# 1_Main.net
KiCad netlist of a schematic drawn in EAGLE
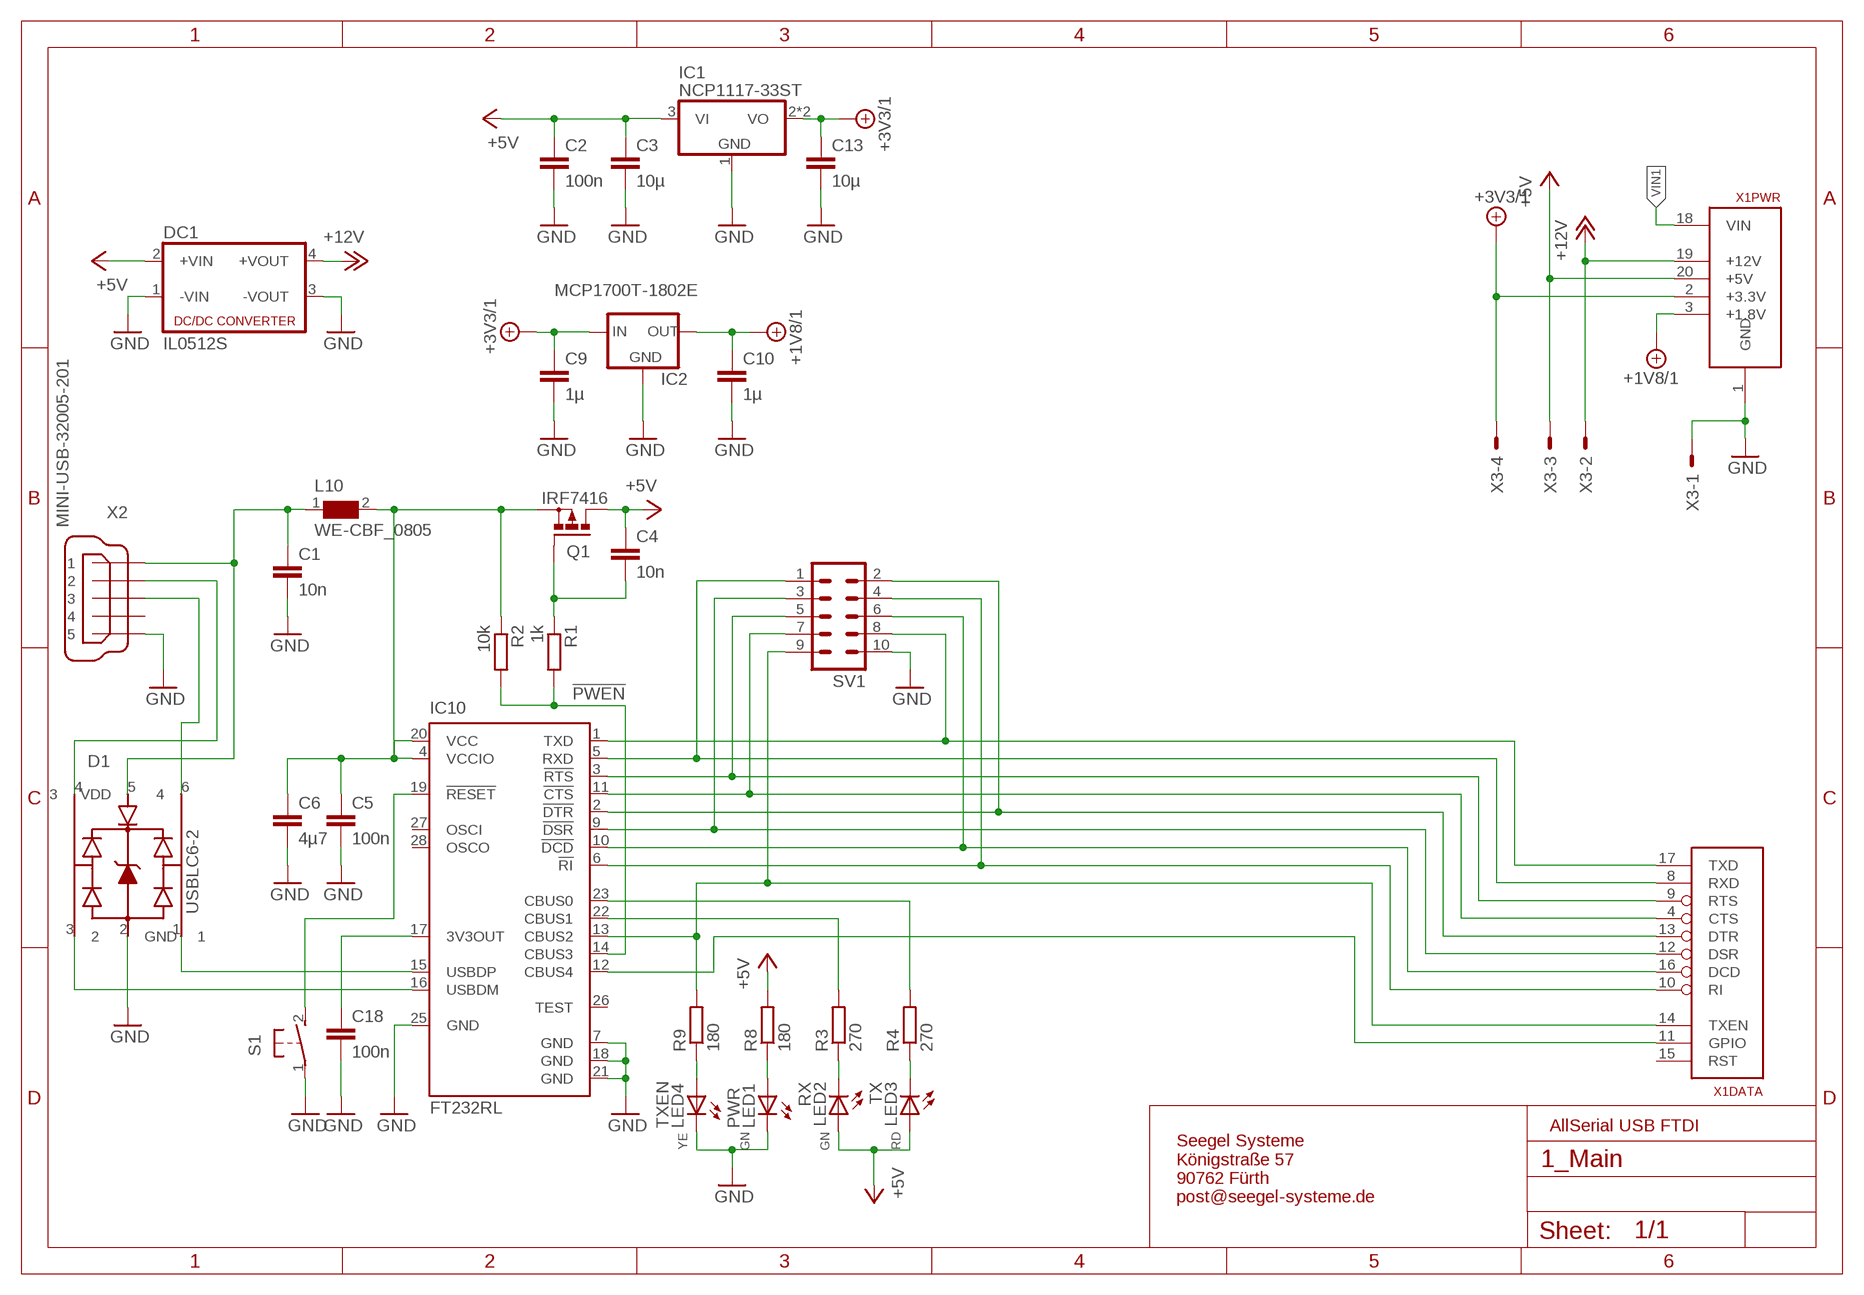
[diagram p0: schematic, sheet 1]

(export (version "E")
  (design (tool "Eeschema 10.0.6"))
  (components
    (comp (ref "C1")
      (value "10n")
      (footprint "eagle-import:C0805")
      (libsource (lib "eagle-import") (part "C-EUC0805"))
    )
    (comp (ref "C2")
      (value "100n")
      (footprint "eagle-import:C0805")
      (libsource (lib "eagle-import") (part "C-EUC0805"))
    )
    (comp (ref "C3")
      (value "10µ")
      (footprint "eagle-import:C0805")
      (libsource (lib "eagle-import") (part "C-EUC0805"))
    )
    (comp (ref "C4")
      (value "10n")
      (footprint "eagle-import:C0805")
      (libsource (lib "eagle-import") (part "C-EUC0805"))
    )
    (comp (ref "C5")
      (value "100n")
      (footprint "eagle-import:C0805")
      (libsource (lib "eagle-import") (part "C-EUC0805"))
    )
    (comp (ref "C6")
      (value "4µ7")
      (footprint "eagle-import:C0805")
      (libsource (lib "eagle-import") (part "C-EUC0805"))
    )
    (comp (ref "C9")
      (value "1µ")
      (footprint "eagle-import:C0805")
      (libsource (lib "eagle-import") (part "C-EUC0805"))
    )
    (comp (ref "C10")
      (value "1µ")
      (footprint "eagle-import:C0805")
      (libsource (lib "eagle-import") (part "C-EUC0805"))
    )
    (comp (ref "C13")
      (value "10µ")
      (footprint "eagle-import:C0805")
      (libsource (lib "eagle-import") (part "C-EUC0805"))
    )
    (comp (ref "C18")
      (value "100n")
      (footprint "eagle-import:C0805")
      (libsource (lib "eagle-import") (part "C-EUC0805"))
    )
    (comp (ref "D1")
      (value "USBLC6-2")
      (footprint "eagle-import:WE-TVS_SOT23-6L")
      (libsource (lib "eagle-import") (part "WE-TVS_82400102"))
    )
    (comp (ref "DC1")
      (value "IL0512S")
      (footprint "eagle-import:NME")
      (fields (field (name "MF") "C & D TECHNOLOGIES, INC") (field (name "MPN") "NME1205D"))
      (libsource (lib "eagle-import") (part "NME"))
    )
    (comp (ref "IC1")
      (value "NCP1117-33ST")
      (footprint "eagle-import:SOT223")
      (libsource (lib "eagle-import") (part "NCP1117ST-33"))
    )
    (comp (ref "IC2")
      (value "MCP1700T-1802E")
      (footprint "eagle-import:SOT23")
      (libsource (lib "eagle-import") (part "MCP170X"))
    )
    (comp (ref "IC10")
      (value "FT232RL")
      (footprint "eagle-import:SSOP28")
      (libsource (lib "eagle-import") (part "FT232RL"))
    )
    (comp (ref "L10")
      (value "WE-CBF_0805")
      (footprint "eagle-import:0805")
      (libsource (lib "eagle-import") (part "WE-CBF_0805"))
    )
    (comp (ref "LED1")
      (value "PWR")
      (footprint "eagle-import:CHIPLED_0603")
      (fields (field (name "COLOR") "GN"))
      (libsource (lib "eagle-import") (part "LEDCHIPLED_0603"))
    )
    (comp (ref "LED2")
      (value "RX")
      (footprint "eagle-import:CHIPLED_0603")
      (fields (field (name "COLOR") "GN"))
      (libsource (lib "eagle-import") (part "LEDCHIPLED_0603"))
    )
    (comp (ref "LED3")
      (value "TX")
      (footprint "eagle-import:CHIPLED_0603")
      (fields (field (name "COLOR") "RD"))
      (libsource (lib "eagle-import") (part "LEDCHIPLED_0603"))
    )
    (comp (ref "LED4")
      (value "TXEN")
      (footprint "eagle-import:CHIPLED_0603")
      (fields (field (name "COLOR") "YE"))
      (libsource (lib "eagle-import") (part "LEDCHIPLED_0603"))
    )
    (comp (ref "Q1")
      (value "IRF7416")
      (footprint "eagle-import:SO-08")
      (libsource (lib "eagle-import") (part "P-MOSFET-SO8"))
    )
    (comp (ref "R1")
      (value "1k")
      (footprint "eagle-import:R0805")
      (libsource (lib "eagle-import") (part "R-EU_R0805"))
    )
    (comp (ref "R2")
      (value "10k")
      (footprint "eagle-import:R0805")
      (libsource (lib "eagle-import") (part "R-EU_R0805"))
    )
    (comp (ref "R3")
      (value "270")
      (footprint "eagle-import:R0805")
      (libsource (lib "eagle-import") (part "R-EU_R0805"))
    )
    (comp (ref "R4")
      (value "270")
      (footprint "eagle-import:R0805")
      (libsource (lib "eagle-import") (part "R-EU_R0805"))
    )
    (comp (ref "R8")
      (value "180")
      (footprint "eagle-import:R0805")
      (libsource (lib "eagle-import") (part "R-EU_R0805"))
    )
    (comp (ref "R9")
      (value "180")
      (footprint "eagle-import:R0805")
      (libsource (lib "eagle-import") (part "R-EU_R0805"))
    )
    (comp (ref "S1")
      (value "31-XX")
      (footprint "eagle-import:B3F-31XX")
      (fields (field (name "MPN") "B3F-3100"))
      (libsource (lib "eagle-import") (part "31-XX"))
    )
    (comp (ref "SV1")
      (value "ML10")
      (footprint "eagle-import:ML10")
      (libsource (lib "eagle-import") (part "ML10"))
    )
    (comp (ref "X1")
      (value "ALLSERIALMASTERMM")
      (footprint "eagle-import:MAIN-THT")
      (libsource (lib "eagle-import") (part "ALLSERIALMASTERMM"))
    )
    (comp (ref "X2")
      (value "MINI-USB-32005-201")
      (footprint "eagle-import:32005-201")
      (libsource (lib "eagle-import") (part "MINI-USB-32005-201"))
    )
    (comp (ref "X3")
      (value "AKL18X-04W")
      (footprint "eagle-import:AKL182-04")
      (libsource (lib "eagle-import") (part "AKL18X-04W"))
    )
  )
  (nets
    (net (code "1") (name "+1V8{slash}1") (class "Default")
      (node (ref "C10") (pin "1") (pinfunction "1_1") (pintype "passive"))
      (node (ref "IC2") (pin "2") (pinfunction "OUT_2") (pintype "passive"))
      (node (ref "X1") (pin "3") (pinfunction "+1.8V_3") (pintype "bidirectional"))
    )
    (net (code "2") (name "+3V3{slash}1") (class "Default")
      (node (ref "C13") (pin "1") (pinfunction "1_1") (pintype "passive"))
      (node (ref "C9") (pin "1") (pinfunction "1_1") (pintype "passive"))
      (node (ref "IC1") (pin "2") (pinfunction "VO_2") (pintype "passive"))
      (node (ref "IC1") (pin "4") (pinfunction "VO_4") (pintype "passive"))
      (node (ref "IC2") (pin "3") (pinfunction "IN_3") (pintype "input"))
      (node (ref "X1") (pin "2") (pinfunction "+3.3V_2") (pintype "bidirectional"))
      (node (ref "X3") (pin "P$4") (pinfunction "S_P$4") (pintype "passive"))
    )
    (net (code "3") (name "+5V") (class "Default")
      (node (ref "C2") (pin "1") (pinfunction "1_1") (pintype "passive"))
      (node (ref "C3") (pin "1") (pinfunction "1_1") (pintype "passive"))
      (node (ref "C4") (pin "1") (pinfunction "1_1") (pintype "passive"))
      (node (ref "DC1") (pin "2") (pinfunction "+VIN_2") (pintype "passive"))
      (node (ref "IC1") (pin "3") (pinfunction "VI_3") (pintype "input"))
      (node (ref "LED2") (pin "A") (pinfunction "A_A") (pintype "passive"))
      (node (ref "LED3") (pin "A") (pinfunction "A_A") (pintype "passive"))
      (node (ref "Q1") (pin "5") (pinfunction "D_5") (pintype "passive"))
      (node (ref "Q1") (pin "6") (pinfunction "D_6") (pintype "passive"))
      (node (ref "Q1") (pin "7") (pinfunction "D_7") (pintype "passive"))
      (node (ref "Q1") (pin "8") (pinfunction "D_8") (pintype "passive"))
      (node (ref "R8") (pin "2") (pinfunction "2_2") (pintype "passive"))
      (node (ref "X1") (pin "20") (pinfunction "+5V_20") (pintype "bidirectional"))
      (node (ref "X3") (pin "P$3") (pinfunction "S_P$3") (pintype "passive"))
    )
    (net (code "4") (name "+12V") (class "Default")
      (node (ref "DC1") (pin "4") (pinfunction "+VOUT_4") (pintype "passive"))
      (node (ref "X1") (pin "19") (pinfunction "+12V_19") (pintype "bidirectional"))
      (node (ref "X3") (pin "P$2") (pinfunction "S_P$2") (pintype "passive"))
    )
    (net (code "5") (name "/~{PWEN}") (class "Default")
      (node (ref "IC10") (pin "14") (pinfunction "CBUS3_14") (pintype "bidirectional"))
      (node (ref "R1") (pin "2") (pinfunction "2_2") (pintype "passive"))
      (node (ref "R2") (pin "2") (pinfunction "2_2") (pintype "passive"))
    )
    (net (code "6") (name "GND") (class "Default")
      (node (ref "C1") (pin "2") (pinfunction "2_2") (pintype "passive"))
      (node (ref "C10") (pin "2") (pinfunction "2_2") (pintype "passive"))
      (node (ref "C13") (pin "2") (pinfunction "2_2") (pintype "passive"))
      (node (ref "C18") (pin "2") (pinfunction "2_2") (pintype "passive"))
      (node (ref "C2") (pin "2") (pinfunction "2_2") (pintype "passive"))
      (node (ref "C3") (pin "2") (pinfunction "2_2") (pintype "passive"))
      (node (ref "C5") (pin "2") (pinfunction "2_2") (pintype "passive"))
      (node (ref "C6") (pin "2") (pinfunction "2_2") (pintype "passive"))
      (node (ref "C9") (pin "2") (pinfunction "2_2") (pintype "passive"))
      (node (ref "D1") (pin "2") (pinfunction "GND_2") (pintype "power_in"))
      (node (ref "DC1") (pin "1") (pinfunction "-VIN_1") (pintype "passive"))
      (node (ref "DC1") (pin "3") (pinfunction "-VOUT_3") (pintype "passive"))
      (node (ref "IC1") (pin "1") (pinfunction "GND_1") (pintype "passive"))
      (node (ref "IC10") (pin "18") (pinfunction "GND_18") (pintype "power_in"))
      (node (ref "IC10") (pin "21") (pinfunction "GND_21") (pintype "power_in"))
      (node (ref "IC10") (pin "25") (pinfunction "GND_25") (pintype "power_in"))
      (node (ref "IC10") (pin "7") (pinfunction "GND_7") (pintype "power_in"))
      (node (ref "IC2") (pin "1") (pinfunction "GND_1") (pintype "input"))
      (node (ref "LED1") (pin "C") (pinfunction "C_C") (pintype "passive"))
      (node (ref "LED4") (pin "C") (pinfunction "C_C") (pintype "passive"))
      (node (ref "S1") (pin "1") (pinfunction "P_1") (pintype "passive"))
      (node (ref "SV1") (pin "10") (pinfunction "10_10") (pintype "passive"))
      (node (ref "X1") (pin "1") (pinfunction "GND_1") (pintype "bidirectional"))
      (node (ref "X2") (pin "5") (pinfunction "5_5") (pintype "passive"))
      (node (ref "X3") (pin "P$1") (pinfunction "S_P$1") (pintype "passive"))
    )
    (net (code "7") (name "Net-(D1-2)") (class "Default")
      (node (ref "D1") (pin "3") (pinfunction "2_3") (pintype "passive"))
      (node (ref "IC10") (pin "16") (pinfunction "USBDM_16") (pintype "bidirectional"))
    )
    (net (code "8") (name "Net-(D1-3)") (class "Default")
      (node (ref "D1") (pin "4") (pinfunction "3_4") (pintype "passive"))
      (node (ref "X2") (pin "2") (pinfunction "2_2") (pintype "passive"))
    )
    (net (code "9") (name "Net-(D1-4)") (class "Default")
      (node (ref "D1") (pin "6") (pinfunction "4_6") (pintype "passive"))
      (node (ref "X2") (pin "3") (pinfunction "3_3") (pintype "passive"))
    )
    (net (code "10") (name "Net-(D1-VDD)") (class "Default")
      (node (ref "C1") (pin "1") (pinfunction "1_1") (pintype "passive"))
      (node (ref "D1") (pin "5") (pinfunction "VDD_5") (pintype "power_in"))
      (node (ref "L10") (pin "1") (pinfunction "1_1") (pintype "passive"))
      (node (ref "X2") (pin "1") (pinfunction "1_1") (pintype "passive"))
    )
    (net (code "11") (name "Net-(IC10-3V3OUT)") (class "Default")
      (node (ref "C18") (pin "1") (pinfunction "1_1") (pintype "passive"))
      (node (ref "IC10") (pin "17") (pinfunction "3V3OUT_17") (pintype "output"))
    )
    (net (code "12") (name "Net-(IC10-CBUS0)") (class "Default")
      (node (ref "IC10") (pin "23") (pinfunction "CBUS0_23") (pintype "bidirectional"))
      (node (ref "R4") (pin "2") (pinfunction "2_2") (pintype "passive"))
    )
    (net (code "13") (name "Net-(IC10-CBUS1)") (class "Default")
      (node (ref "IC10") (pin "22") (pinfunction "CBUS1_22") (pintype "bidirectional"))
      (node (ref "R3") (pin "2") (pinfunction "2_2") (pintype "passive"))
    )
    (net (code "14") (name "Net-(IC10-CBUS2)") (class "Default")
      (node (ref "IC10") (pin "13") (pinfunction "CBUS2_13") (pintype "bidirectional"))
      (node (ref "R9") (pin "2") (pinfunction "2_2") (pintype "passive"))
      (node (ref "SV1") (pin "9") (pinfunction "9_9") (pintype "passive"))
      (node (ref "X1") (pin "14") (pinfunction "TXEN_14") (pintype "input"))
    )
    (net (code "15") (name "Net-(IC10-CBUS4)") (class "Default")
      (node (ref "IC10") (pin "12") (pinfunction "CBUS4_12") (pintype "bidirectional"))
      (node (ref "X1") (pin "11") (pinfunction "GPIO_11") (pintype "bidirectional"))
    )
    (net (code "16") (name "Net-(IC10-RXD)") (class "Default")
      (node (ref "IC10") (pin "5") (pinfunction "RXD_5") (pintype "input"))
      (node (ref "SV1") (pin "1") (pinfunction "1_1") (pintype "passive"))
      (node (ref "X1") (pin "8") (pinfunction "RXD_8") (pintype "output"))
    )
    (net (code "17") (name "Net-(IC10-TXD)") (class "Default")
      (node (ref "IC10") (pin "1") (pinfunction "TXD_1") (pintype "output"))
      (node (ref "SV1") (pin "8") (pinfunction "8_8") (pintype "passive"))
      (node (ref "X1") (pin "17") (pinfunction "TXD_17") (pintype "input"))
    )
    (net (code "18") (name "Net-(IC10-USBDP)") (class "Default")
      (node (ref "D1") (pin "1") (pinfunction "1_1") (pintype "passive"))
      (node (ref "IC10") (pin "15") (pinfunction "USBDP_15") (pintype "bidirectional"))
    )
    (net (code "19") (name "Net-(IC10-VCC)") (class "Default")
      (node (ref "C5") (pin "1") (pinfunction "1_1") (pintype "passive"))
      (node (ref "C6") (pin "1") (pinfunction "1_1") (pintype "passive"))
      (node (ref "IC10") (pin "20") (pinfunction "VCC_20") (pintype "power_in"))
      (node (ref "IC10") (pin "4") (pinfunction "VCCIO_4") (pintype "power_in"))
      (node (ref "L10") (pin "2") (pinfunction "2_2") (pintype "passive"))
      (node (ref "Q1") (pin "1") (pinfunction "S_1") (pintype "passive"))
      (node (ref "Q1") (pin "2") (pinfunction "S_2") (pintype "passive"))
      (node (ref "Q1") (pin "3") (pinfunction "S_3") (pintype "passive"))
      (node (ref "R2") (pin "1") (pinfunction "1_1") (pintype "passive"))
    )
    (net (code "20") (name "Net-(IC10-~{CTS})") (class "Default")
      (node (ref "IC10") (pin "11") (pinfunction "~{CTS}_11") (pintype "input"))
      (node (ref "SV1") (pin "7") (pinfunction "7_7") (pintype "passive"))
      (node (ref "X1") (pin "4") (pinfunction "CTS_4") (pintype "output"))
    )
    (net (code "21") (name "Net-(IC10-~{DCD})") (class "Default")
      (node (ref "IC10") (pin "10") (pinfunction "~{DCD}_10") (pintype "input"))
      (node (ref "SV1") (pin "6") (pinfunction "6_6") (pintype "passive"))
      (node (ref "X1") (pin "16") (pinfunction "DCD_16") (pintype "output"))
    )
    (net (code "22") (name "Net-(IC10-~{DSR})") (class "Default")
      (node (ref "IC10") (pin "9") (pinfunction "~{DSR}_9") (pintype "input"))
      (node (ref "SV1") (pin "3") (pinfunction "3_3") (pintype "passive"))
      (node (ref "X1") (pin "12") (pinfunction "DSR_12") (pintype "output"))
    )
    (net (code "23") (name "Net-(IC10-~{DTR})") (class "Default")
      (node (ref "IC10") (pin "2") (pinfunction "~{DTR}_2") (pintype "output"))
      (node (ref "SV1") (pin "2") (pinfunction "2_2") (pintype "passive"))
      (node (ref "X1") (pin "13") (pinfunction "DTR_13") (pintype "input"))
    )
    (net (code "24") (name "Net-(IC10-~{RESET})") (class "Default")
      (node (ref "IC10") (pin "19") (pinfunction "~{RESET}_19") (pintype "input"))
      (node (ref "S1") (pin "2") (pinfunction "S_2") (pintype "passive"))
    )
    (net (code "25") (name "Net-(IC10-~{RI})") (class "Default")
      (node (ref "IC10") (pin "6") (pinfunction "~{RI}_6") (pintype "input"))
      (node (ref "SV1") (pin "4") (pinfunction "4_4") (pintype "passive"))
      (node (ref "X1") (pin "10") (pinfunction "RI_10") (pintype "output"))
    )
    (net (code "26") (name "Net-(IC10-~{RTS})") (class "Default")
      (node (ref "IC10") (pin "3") (pinfunction "~{RTS}_3") (pintype "output"))
      (node (ref "SV1") (pin "5") (pinfunction "5_5") (pintype "passive"))
      (node (ref "X1") (pin "9") (pinfunction "RTS_9") (pintype "input"))
    )
    (net (code "27") (name "Net-(LED1-PadA)") (class "Default")
      (node (ref "LED1") (pin "A") (pinfunction "A_A") (pintype "passive"))
      (node (ref "R8") (pin "1") (pinfunction "1_1") (pintype "passive"))
    )
    (net (code "28") (name "Net-(LED2-PadC)") (class "Default")
      (node (ref "LED2") (pin "C") (pinfunction "C_C") (pintype "passive"))
      (node (ref "R3") (pin "1") (pinfunction "1_1") (pintype "passive"))
    )
    (net (code "29") (name "Net-(LED3-PadC)") (class "Default")
      (node (ref "LED3") (pin "C") (pinfunction "C_C") (pintype "passive"))
      (node (ref "R4") (pin "1") (pinfunction "1_1") (pintype "passive"))
    )
    (net (code "30") (name "Net-(LED4-PadA)") (class "Default")
      (node (ref "LED4") (pin "A") (pinfunction "A_A") (pintype "passive"))
      (node (ref "R9") (pin "1") (pinfunction "1_1") (pintype "passive"))
    )
    (net (code "31") (name "Net-(Q1-G)") (class "Default")
      (node (ref "C4") (pin "2") (pinfunction "2_2") (pintype "passive"))
      (node (ref "Q1") (pin "4") (pinfunction "G_4") (pintype "passive"))
      (node (ref "R1") (pin "1") (pinfunction "1_1") (pintype "passive"))
    )
    (net (code "32") (name "VIN1") (class "Default")
      (node (ref "X1") (pin "18") (pinfunction "VIN_18") (pintype "bidirectional"))
    )
    (net (code "33") (name "unconnected-(IC10-OSCI-Pad27)") (class "Default")
      (node (ref "IC10") (pin "27") (pinfunction "OSCI_27") (pintype "input"))
    )
    (net (code "34") (name "unconnected-(IC10-OSCO-Pad28)") (class "Default")
      (node (ref "IC10") (pin "28") (pinfunction "OSCO_28") (pintype "output"))
    )
    (net (code "35") (name "unconnected-(IC10-TEST-Pad26)") (class "Default")
      (node (ref "IC10") (pin "26") (pinfunction "TEST_26") (pintype "input"))
    )
    (net (code "36") (name "unconnected-(X1A-RST-Pad15)") (class "Default")
      (node (ref "X1") (pin "15") (pinfunction "RST_15") (pintype "bidirectional"))
    )
    (net (code "37") (name "unconnected-(X2-Pad4)") (class "Default")
      (node (ref "X2") (pin "4") (pinfunction "4_4") (pintype "passive"))
    )
  )
)
